# astabil.net
KiCad netlist of a schematic drawn in EAGLE
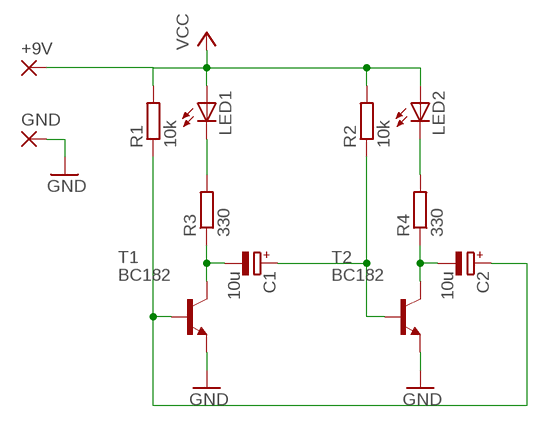
[diagram p0: schematic, sheet 1]

(export (version "E")
  (design (tool "Eeschema 10.0.6"))
  (components
    (comp (ref "+9V")
      (value "2,54/1,0")
      (footprint "eagle-import:2,54_1,0")
      (libsource (lib "eagle-import") (part "2,54/1,0"))
    )
    (comp (ref "C1")
      (value "10u")
      (footprint "eagle-import:E3,5-8")
      (libsource (lib "eagle-import") (part "CPOL-EUE3.5-8"))
    )
    (comp (ref "C2")
      (value "10u")
      (footprint "eagle-import:E3,5-8")
      (libsource (lib "eagle-import") (part "CPOL-EUE3.5-8"))
    )
    (comp (ref "GND")
      (value "2,54/1,0")
      (footprint "eagle-import:2,54_1,0")
      (libsource (lib "eagle-import") (part "2,54/1,0"))
    )
    (comp (ref "LED1")
      (value "LED5MM")
      (footprint "eagle-import:LED5MM")
      (libsource (lib "eagle-import") (part "LED5MM"))
    )
    (comp (ref "LED2")
      (value "LED5MM")
      (footprint "eagle-import:LED5MM")
      (libsource (lib "eagle-import") (part "LED5MM"))
    )
    (comp (ref "R1")
      (value "10k")
      (footprint "eagle-import:0207_10")
      (libsource (lib "eagle-import") (part "R-EU_0207/10"))
    )
    (comp (ref "R2")
      (value "10k")
      (footprint "eagle-import:0207_10")
      (libsource (lib "eagle-import") (part "R-EU_0207/10"))
    )
    (comp (ref "R3")
      (value "330")
      (footprint "eagle-import:0207_10")
      (libsource (lib "eagle-import") (part "R-EU_0207/10"))
    )
    (comp (ref "R4")
      (value "330")
      (footprint "eagle-import:0207_10")
      (libsource (lib "eagle-import") (part "R-EU_0207/10"))
    )
    (comp (ref "T1")
      (value "BC182")
      (footprint "eagle-import:TO92-CBE")
      (libsource (lib "eagle-import") (part "-NPN-TO92-CBEBC547"))
    )
    (comp (ref "T2")
      (value "BC182")
      (footprint "eagle-import:TO92-CBE")
      (libsource (lib "eagle-import") (part "-NPN-TO92-CBEBC547"))
    )
  )
  (nets
    (net (code "1") (name "GND") (class "Default")
      (node (ref "GND") (pin "1") (pinfunction "P_1") (pintype "passive"))
      (node (ref "T1") (pin "E") (pinfunction "E_E") (pintype "passive"))
      (node (ref "T2") (pin "E") (pinfunction "E_E") (pintype "passive"))
    )
    (net (code "2") (name "Net-(C1-Pad+)") (class "Default")
      (node (ref "C1") (pin "+") (pinfunction "+_+") (pintype "passive"))
      (node (ref "R2") (pin "1") (pinfunction "1_1") (pintype "passive"))
      (node (ref "T2") (pin "B") (pinfunction "B_B") (pintype "passive"))
    )
    (net (code "3") (name "Net-(C1-Pad-)") (class "Default")
      (node (ref "C1") (pin "-") (pinfunction "-_-") (pintype "passive"))
      (node (ref "R3") (pin "1") (pinfunction "1_1") (pintype "passive"))
      (node (ref "T1") (pin "C") (pinfunction "C_C") (pintype "passive"))
    )
    (net (code "4") (name "Net-(C2-Pad+)") (class "Default")
      (node (ref "C2") (pin "+") (pinfunction "+_+") (pintype "passive"))
      (node (ref "R1") (pin "1") (pinfunction "1_1") (pintype "passive"))
      (node (ref "T1") (pin "B") (pinfunction "B_B") (pintype "passive"))
    )
    (net (code "5") (name "Net-(C2-Pad-)") (class "Default")
      (node (ref "C2") (pin "-") (pinfunction "-_-") (pintype "passive"))
      (node (ref "R4") (pin "1") (pinfunction "1_1") (pintype "passive"))
      (node (ref "T2") (pin "C") (pinfunction "C_C") (pintype "passive"))
    )
    (net (code "6") (name "Net-(LED1-C)") (class "Default")
      (node (ref "LED1") (pin "K") (pinfunction "C_K") (pintype "passive"))
      (node (ref "R3") (pin "2") (pinfunction "2_2") (pintype "passive"))
    )
    (net (code "7") (name "Net-(LED2-C)") (class "Default")
      (node (ref "LED2") (pin "K") (pinfunction "C_K") (pintype "passive"))
      (node (ref "R4") (pin "2") (pinfunction "2_2") (pintype "passive"))
    )
    (net (code "8") (name "VCC") (class "Default")
      (node (ref "+9V") (pin "1") (pinfunction "P_1") (pintype "passive"))
      (node (ref "LED1") (pin "A") (pinfunction "A_A") (pintype "passive"))
      (node (ref "LED2") (pin "A") (pinfunction "A_A") (pintype "passive"))
      (node (ref "R1") (pin "2") (pinfunction "2_2") (pintype "passive"))
      (node (ref "R2") (pin "2") (pinfunction "2_2") (pintype "passive"))
    )
  )
)
